# Geiger.net
KiCad netlist of a schematic drawn in EAGLE
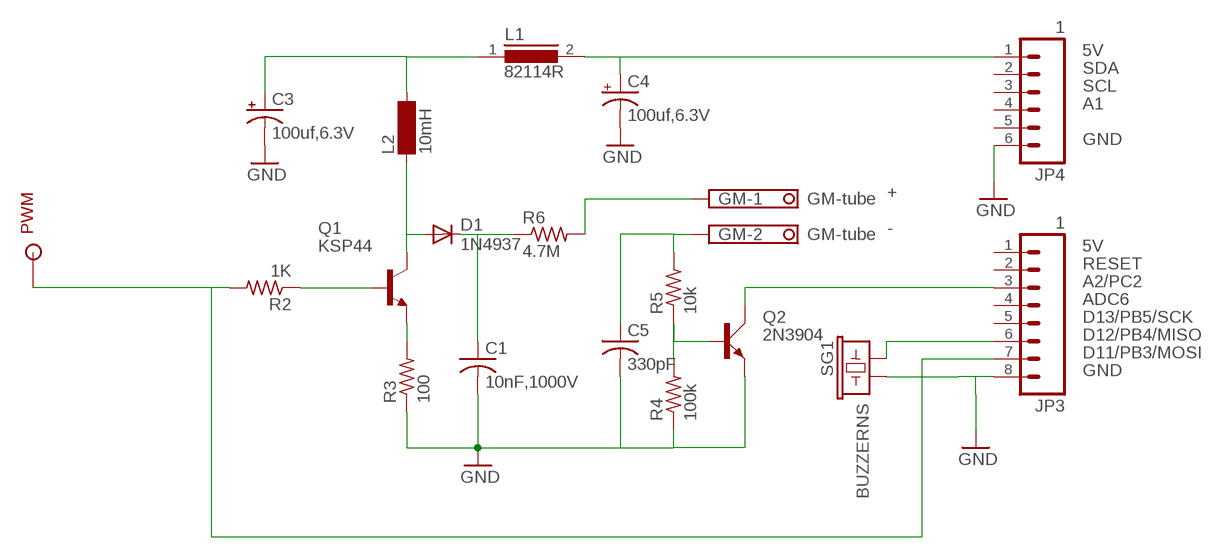
[diagram p0: schematic, sheet 1]

(export (version "E")
  (design (tool "Eeschema 10.0.6"))
  (components
    (comp (ref "C1")
      (value "10nF,1000V")
      (footprint "eagle-import:C150-054X183")
      (libsource (lib "eagle-import") (part "C-US150-054X183"))
    )
    (comp (ref "C3")
      (value "100uf,6.3V")
      (footprint "eagle-import:E2,5-7")
      (libsource (lib "eagle-import") (part "CPOL-USE2.5-7"))
    )
    (comp (ref "C4")
      (value "100uf,6.3V")
      (footprint "eagle-import:E2,5-7")
      (libsource (lib "eagle-import") (part "CPOL-USE2.5-7"))
    )
    (comp (ref "C5")
      (value "330pF")
      (footprint "eagle-import:C050-045X075")
      (libsource (lib "eagle-import") (part "C-US050-045X075"))
    )
    (comp (ref "D1")
      (value "1N4937")
      (footprint "eagle-import:DO41-10")
      (libsource (lib "eagle-import") (part "1N4933"))
    )
    (comp (ref "GM")
      (value "GM-tube")
      (footprint "eagle-import:1751248")
      (libsource (lib "eagle-import") (part "1751248"))
    )
    (comp (ref "JP3")
      (value "1")
      (footprint "eagle-import:1X08")
      (libsource (lib "eagle-import") (part "M081X08"))
    )
    (comp (ref "JP4")
      (value "1")
      (footprint "eagle-import:1X06")
      (libsource (lib "eagle-import") (part "M06SIP"))
    )
    (comp (ref "L1")
      (value "82114R")
      (footprint "eagle-import:82114R")
      (libsource (lib "eagle-import") (part "82114R"))
    )
    (comp (ref "L2")
      (value "10mH")
      (footprint "eagle-import:BS11")
      (libsource (lib "eagle-import") (part "BS11"))
    )
    (comp (ref "PWM")
      (value "SOLDER_POINTA")
      (footprint "eagle-import:P1-13")
      (libsource (lib "eagle-import") (part "SOLDER_POINTA"))
    )
    (comp (ref "Q1")
      (value "KSP44")
      (footprint "eagle-import:TO92-CBE")
      (libsource (lib "eagle-import") (part "BC550TO92-CBE"))
    )
    (comp (ref "Q2")
      (value "2N3904")
      (footprint "eagle-import:TO92D")
      (libsource (lib "eagle-import") (part "2N3904"))
    )
    (comp (ref "R2")
      (value "1K")
      (footprint "eagle-import:0207_10")
      (libsource (lib "eagle-import") (part "R-US_0207/10"))
    )
    (comp (ref "R3")
      (value "100")
      (footprint "eagle-import:0207_10")
      (libsource (lib "eagle-import") (part "R-US_0207/10"))
    )
    (comp (ref "R4")
      (value "100k")
      (footprint "eagle-import:0207_10")
      (libsource (lib "eagle-import") (part "R-US_0207/10"))
    )
    (comp (ref "R5")
      (value "10k")
      (footprint "eagle-import:0207_10")
      (libsource (lib "eagle-import") (part "R-US_0207/10"))
    )
    (comp (ref "R6")
      (value "4.7M")
      (footprint "eagle-import:0207_10")
      (libsource (lib "eagle-import") (part "R-US_0207/10"))
    )
    (comp (ref "SG1")
      (value "BUZZERNS")
      (footprint "eagle-import:BUZZER-12MM-NS")
      (libsource (lib "eagle-import") (part "BUZZERNS"))
    )
  )
  (nets
    (net (code "1") (name "/RESET") (class "Default")
      (node (ref "JP3") (pin "3") (pinfunction "3_3") (pintype "passive"))
      (node (ref "Q2") (pin "C") (pinfunction "C_C") (pintype "passive"))
    )
    (net (code "2") (name "GND") (class "Default")
      (node (ref "C1") (pin "2") (pinfunction "2_2") (pintype "passive"))
      (node (ref "C3") (pin "-") (pinfunction "-_-") (pintype "passive"))
      (node (ref "C4") (pin "-") (pinfunction "-_-") (pintype "passive"))
      (node (ref "C5") (pin "2") (pinfunction "2_2") (pintype "passive"))
      (node (ref "JP3") (pin "8") (pinfunction "8_8") (pintype "passive"))
      (node (ref "JP4") (pin "6") (pinfunction "6_6") (pintype "passive"))
      (node (ref "Q2") (pin "E") (pinfunction "E_E") (pintype "passive"))
      (node (ref "R3") (pin "1") (pinfunction "1_1") (pintype "passive"))
      (node (ref "R4") (pin "1") (pinfunction "1_1") (pintype "passive"))
      (node (ref "SG1") (pin "-") (pinfunction "2_-") (pintype "passive"))
    )
    (net (code "3") (name "Net-(C1-Pad1)") (class "Default")
      (node (ref "C1") (pin "1") (pinfunction "1_1") (pintype "passive"))
      (node (ref "D1") (pin "C") (pinfunction "C_C") (pintype "passive"))
      (node (ref "R6") (pin "1") (pinfunction "1_1") (pintype "passive"))
    )
    (net (code "4") (name "Net-(C3-Pad+)") (class "Default")
      (node (ref "C3") (pin "+") (pinfunction "+_+") (pintype "passive"))
      (node (ref "L1") (pin "1") (pinfunction "1_1") (pintype "passive"))
      (node (ref "L2") (pin "2") (pinfunction "2_2") (pintype "passive"))
    )
    (net (code "5") (name "Net-(C4-Pad+)") (class "Default")
      (node (ref "C4") (pin "+") (pinfunction "+_+") (pintype "passive"))
      (node (ref "JP4") (pin "1") (pinfunction "1_1") (pintype "passive"))
      (node (ref "L1") (pin "2") (pinfunction "2_2") (pintype "passive"))
    )
    (net (code "6") (name "Net-(D1-PadA)") (class "Default")
      (node (ref "D1") (pin "A") (pinfunction "A_A") (pintype "passive"))
      (node (ref "L2") (pin "1") (pinfunction "1_1") (pintype "passive"))
      (node (ref "Q1") (pin "C") (pinfunction "C_C") (pintype "passive"))
    )
    (net (code "7") (name "Net-(GMA-K)") (class "Default")
      (node (ref "GM") (pin "1") (pinfunction "K_1") (pintype "passive"))
      (node (ref "R6") (pin "2") (pinfunction "2_2") (pintype "passive"))
    )
    (net (code "8") (name "Net-(GMB-K)") (class "Default")
      (node (ref "C5") (pin "1") (pinfunction "1_1") (pintype "passive"))
      (node (ref "GM") (pin "2") (pinfunction "K_2") (pintype "passive"))
      (node (ref "R5") (pin "2") (pinfunction "2_2") (pintype "passive"))
    )
    (net (code "9") (name "Net-(PWM-P$1)") (class "Default")
      (node (ref "JP3") (pin "7") (pinfunction "7_7") (pintype "passive"))
      (node (ref "PWM") (pin "1") (pinfunction "P$1_1") (pintype "bidirectional"))
      (node (ref "R2") (pin "2") (pinfunction "2_2") (pintype "passive"))
    )
    (net (code "10") (name "Net-(Q1-PadB)") (class "Default")
      (node (ref "Q1") (pin "B") (pinfunction "B_B") (pintype "passive"))
      (node (ref "R2") (pin "1") (pinfunction "1_1") (pintype "passive"))
    )
    (net (code "11") (name "Net-(Q1-PadE)") (class "Default")
      (node (ref "Q1") (pin "E") (pinfunction "E_E") (pintype "passive"))
      (node (ref "R3") (pin "2") (pinfunction "2_2") (pintype "passive"))
    )
    (net (code "12") (name "Net-(Q2-PadB)") (class "Default")
      (node (ref "Q2") (pin "B") (pinfunction "B_B") (pintype "passive"))
      (node (ref "R4") (pin "2") (pinfunction "2_2") (pintype "passive"))
      (node (ref "R5") (pin "1") (pinfunction "1_1") (pintype "passive"))
    )
    (net (code "13") (name "Net-(SG1-1)") (class "Default")
      (node (ref "JP3") (pin "6") (pinfunction "6_6") (pintype "passive"))
      (node (ref "SG1") (pin "+") (pinfunction "1_+") (pintype "passive"))
    )
    (net (code "14") (name "unconnected-(JP3-Pad1)") (class "Default")
      (node (ref "JP3") (pin "1") (pinfunction "1_1") (pintype "passive"))
    )
    (net (code "15") (name "unconnected-(JP3-Pad2)") (class "Default")
      (node (ref "JP3") (pin "2") (pinfunction "2_2") (pintype "passive"))
    )
    (net (code "16") (name "unconnected-(JP3-Pad4)") (class "Default")
      (node (ref "JP3") (pin "4") (pinfunction "4_4") (pintype "passive"))
    )
    (net (code "17") (name "unconnected-(JP3-Pad5)") (class "Default")
      (node (ref "JP3") (pin "5") (pinfunction "5_5") (pintype "passive"))
    )
    (net (code "18") (name "unconnected-(JP4-Pad2)") (class "Default")
      (node (ref "JP4") (pin "2") (pinfunction "2_2") (pintype "passive"))
    )
    (net (code "19") (name "unconnected-(JP4-Pad3)") (class "Default")
      (node (ref "JP4") (pin "3") (pinfunction "3_3") (pintype "passive"))
    )
    (net (code "20") (name "unconnected-(JP4-Pad4)") (class "Default")
      (node (ref "JP4") (pin "4") (pinfunction "4_4") (pintype "passive"))
    )
    (net (code "21") (name "unconnected-(JP4-Pad5)") (class "Default")
      (node (ref "JP4") (pin "5") (pinfunction "5_5") (pintype "passive"))
    )
  )
)
